# Schematic.net
KiCad netlist of a schematic drawn in Altium Designer
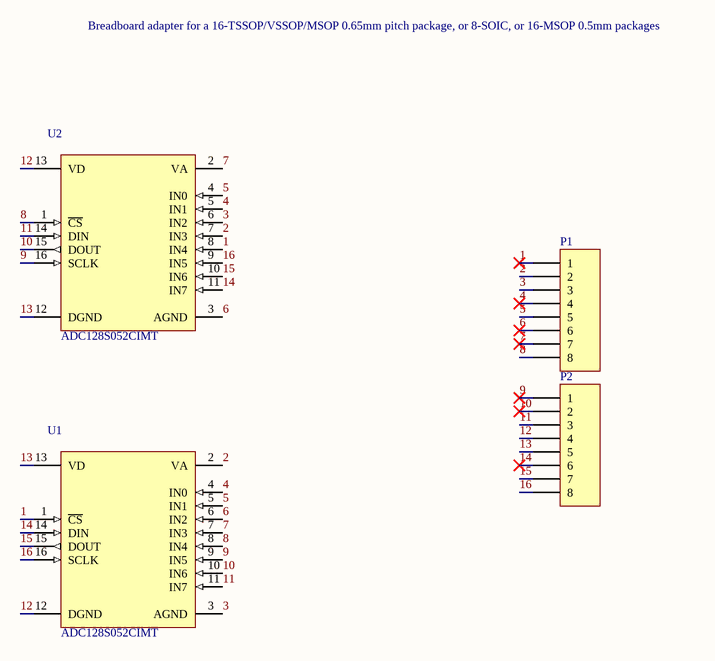
[diagram p0: Schematic.SchDoc]

(export (version "E")
  (design (tool "Eeschema 10.0.6"))
  (components
    (comp (ref "P1")
      (value "~")
      (footprint "HDR1X8")
      (description "Header, 8-Pin")
      (fields (field (name "PUBLISHER") "Altium Limited"))
      (libsource (lib "Miscellaneous Connectors") (part "Header 8"))
    )
    (comp (ref "P2")
      (value "~")
      (footprint "HDR1X8")
      (description "Header, 8-Pin")
      (fields (field (name "PUBLISHER") "Altium Limited"))
      (libsource (lib "Miscellaneous Connectors") (part "Header 8"))
    )
    (comp (ref "U1")
      (value "ADC128S052CIMT")
      (footprint "TSSOP/VSSOP/MSOP-0.65mm-16,SOIC-8")
      (description "8-Channel 12-Bit ADC")
      (fields (field (name "MF") "Texas Instruments") (field (name "MP") "ADC128S052CIMT/NOPB"))
      (libsource (lib "General Components") (part "ADC128S052CIMT"))
    )
    (comp (ref "U2")
      (value "ADC128S052CIMT")
      (footprint "MSOP-0.5mmPitch-16N-3mmBody-1.1mm")
      (description "8-Channel 12-Bit ADC")
      (fields (field (name "MF") "Texas Instruments") (field (name "MP") "ADC128S052CIMT/NOPB"))
      (libsource (lib "General Components") (part "ADC128S052CIMT"))
    )
  )
  (nets
    (net (code "1") (name "/1") (class "Default")
      (node (ref "P1") (pin "1") (pinfunction "1_1") (pintype "passive"))
      (node (ref "U1") (pin "1") (pinfunction "~{CS}_1") (pintype "input"))
      (node (ref "U2") (pin "8") (pinfunction "IN4_8") (pintype "input"))
    )
    (net (code "2") (name "/2") (class "Default")
      (node (ref "P1") (pin "2") (pinfunction "2_2") (pintype "passive"))
      (node (ref "U1") (pin "2") (pinfunction "VA_2") (pintype "power_in"))
      (node (ref "U2") (pin "7") (pinfunction "IN3_7") (pintype "input"))
    )
    (net (code "3") (name "/3") (class "Default")
      (node (ref "P1") (pin "3") (pinfunction "3_3") (pintype "passive"))
      (node (ref "U1") (pin "3") (pinfunction "AGND_3") (pintype "passive"))
      (node (ref "U2") (pin "6") (pinfunction "IN2_6") (pintype "input"))
    )
    (net (code "4") (name "/4") (class "Default")
      (node (ref "P1") (pin "4") (pinfunction "4_4") (pintype "passive"))
      (node (ref "U1") (pin "4") (pinfunction "IN0_4") (pintype "input"))
      (node (ref "U2") (pin "5") (pinfunction "IN1_5") (pintype "input"))
    )
    (net (code "5") (name "/5") (class "Default")
      (node (ref "P1") (pin "5") (pinfunction "5_5") (pintype "passive"))
      (node (ref "U1") (pin "5") (pinfunction "IN1_5") (pintype "input"))
      (node (ref "U2") (pin "4") (pinfunction "IN0_4") (pintype "input"))
    )
    (net (code "6") (name "/6") (class "Default")
      (node (ref "P1") (pin "6") (pinfunction "6_6") (pintype "passive"))
      (node (ref "U1") (pin "6") (pinfunction "IN2_6") (pintype "input"))
      (node (ref "U2") (pin "3") (pinfunction "AGND_3") (pintype "passive"))
    )
    (net (code "7") (name "/7") (class "Default")
      (node (ref "P1") (pin "7") (pinfunction "7_7") (pintype "passive"))
      (node (ref "U1") (pin "7") (pinfunction "IN3_7") (pintype "input"))
      (node (ref "U2") (pin "2") (pinfunction "VA_2") (pintype "power_in"))
    )
    (net (code "8") (name "/8") (class "Default")
      (node (ref "P1") (pin "8") (pinfunction "8_8") (pintype "passive"))
      (node (ref "U1") (pin "8") (pinfunction "IN4_8") (pintype "input"))
      (node (ref "U2") (pin "1") (pinfunction "~{CS}_1") (pintype "input"))
    )
    (net (code "9") (name "/9") (class "Default")
      (node (ref "P2") (pin "1") (pinfunction "1_1") (pintype "passive"))
      (node (ref "U1") (pin "9") (pinfunction "IN5_9") (pintype "input"))
      (node (ref "U2") (pin "16") (pinfunction "SCLK_16") (pintype "input"))
    )
    (net (code "10") (name "/10") (class "Default")
      (node (ref "P2") (pin "2") (pinfunction "2_2") (pintype "passive"))
      (node (ref "U1") (pin "10") (pinfunction "IN6_10") (pintype "input"))
      (node (ref "U2") (pin "15") (pinfunction "DOUT_15") (pintype "output"))
    )
    (net (code "11") (name "/11") (class "Default")
      (node (ref "P2") (pin "3") (pinfunction "3_3") (pintype "passive"))
      (node (ref "U1") (pin "11") (pinfunction "IN7_11") (pintype "input"))
      (node (ref "U2") (pin "14") (pinfunction "DIN_14") (pintype "input"))
    )
    (net (code "12") (name "/12") (class "Default")
      (node (ref "P2") (pin "4") (pinfunction "4_4") (pintype "passive"))
      (node (ref "U1") (pin "12") (pinfunction "DGND_12") (pintype "passive"))
      (node (ref "U2") (pin "13") (pinfunction "VD_13") (pintype "power_in"))
    )
    (net (code "13") (name "/13") (class "Default")
      (node (ref "P2") (pin "5") (pinfunction "5_5") (pintype "passive"))
      (node (ref "U1") (pin "13") (pinfunction "VD_13") (pintype "power_in"))
      (node (ref "U2") (pin "12") (pinfunction "DGND_12") (pintype "passive"))
    )
    (net (code "14") (name "/14") (class "Default")
      (node (ref "P2") (pin "6") (pinfunction "6_6") (pintype "passive"))
      (node (ref "U1") (pin "14") (pinfunction "DIN_14") (pintype "input"))
      (node (ref "U2") (pin "11") (pinfunction "IN7_11") (pintype "input"))
    )
    (net (code "15") (name "/15") (class "Default")
      (node (ref "P2") (pin "7") (pinfunction "7_7") (pintype "passive"))
      (node (ref "U1") (pin "15") (pinfunction "DOUT_15") (pintype "output"))
      (node (ref "U2") (pin "10") (pinfunction "IN6_10") (pintype "input"))
    )
    (net (code "16") (name "/16") (class "Default")
      (node (ref "P2") (pin "8") (pinfunction "8_8") (pintype "passive"))
      (node (ref "U1") (pin "16") (pinfunction "SCLK_16") (pintype "input"))
      (node (ref "U2") (pin "9") (pinfunction "IN5_9") (pintype "input"))
    )
  )
)
